# user.net
KiCad netlist of a schematic drawn in Altium Designer
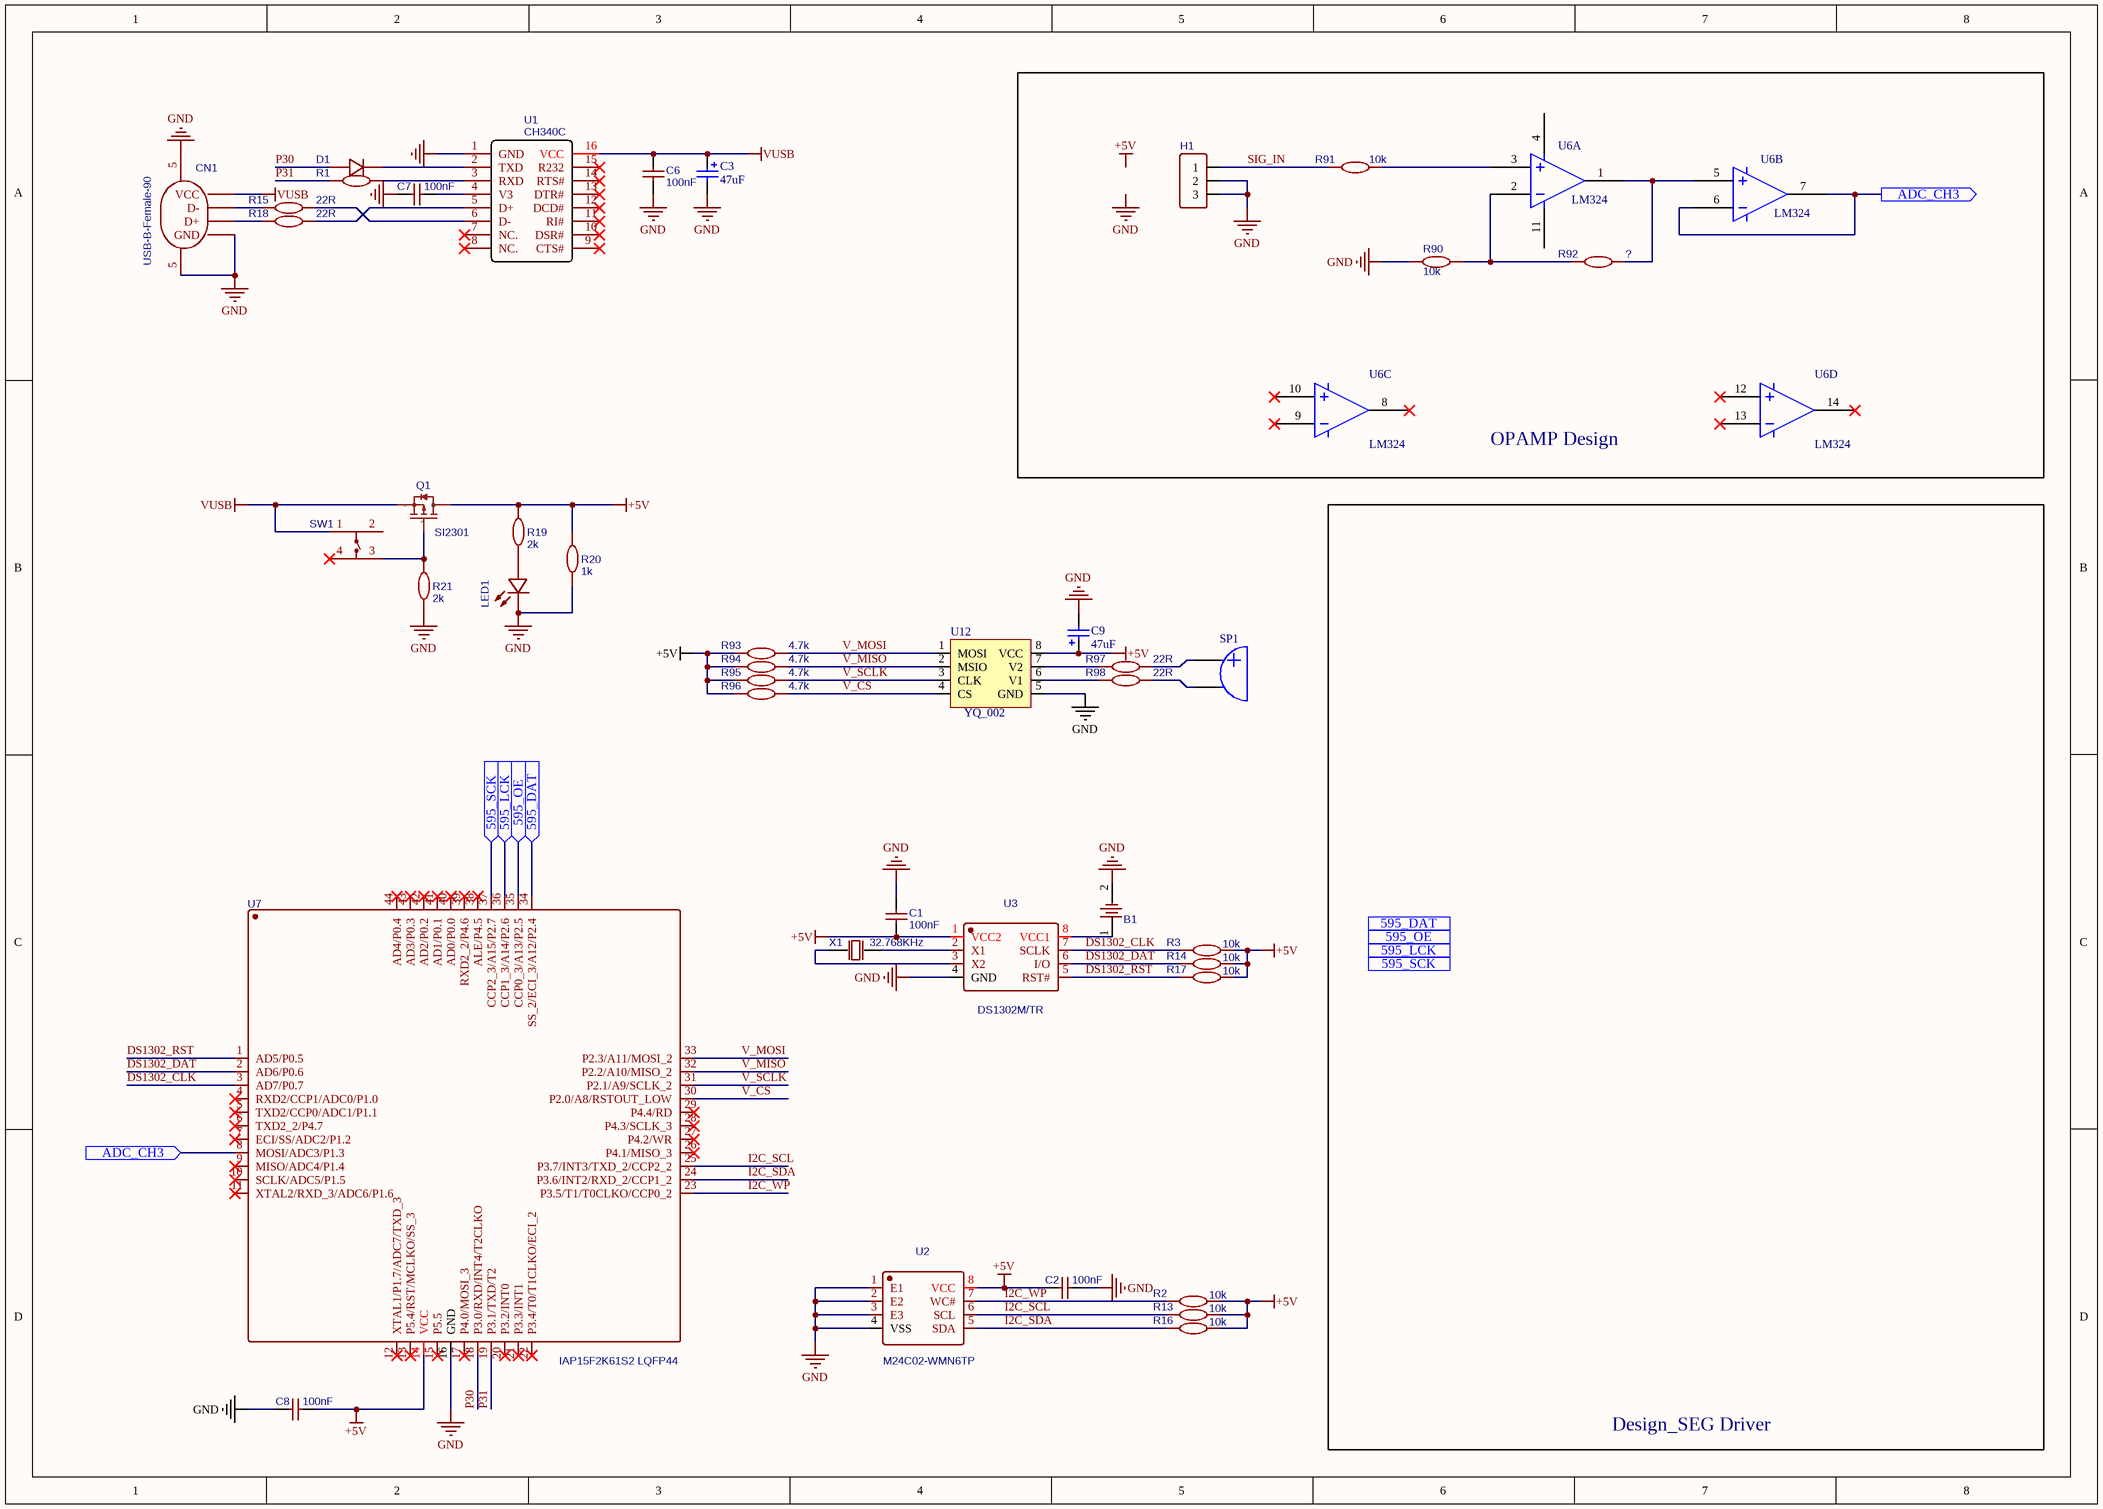
[diagram p0: user.SchDoc]

(export (version "E")
  (design (tool "Eeschema 10.0.6"))
  (components
    (comp (ref "B1")
      (value "CR1220-2")
      (fields (field (name "BOM_SUPPLIER PART") "C70381"))
      (libsource (lib "altium-import") (part "root_1_CR1220-2_"))
    )
    (comp (ref "C1")
      (value "100nF")
      (fields
        (field (name "BOM_MANUFACTURER PART") "0805F104M500NT")
        (field (name "BOM_SUPPLIER PART") "C28378")
      )
      (libsource (lib "altium-import") (part "root_1_100nF_"))
    )
    (comp (ref "C2")
      (value "100nF")
      (fields
        (field (name "BOM_MANUFACTURER PART") "0805F104M500NT")
        (field (name "BOM_SUPPLIER PART") "C28378")
      )
      (libsource (lib "altium-import") (part "root_0_100nF_"))
    )
    (comp (ref "C3")
      (value "47uF")
      (description "Polarized Capacitor (Axial)")
      (libsource (lib "Miscellaneous Devices") (part "Cap Pol2"))
    )
    (comp (ref "C6")
      (value "100nF")
      (fields
        (field (name "BOM_MANUFACTURER PART") "0805F104M500NT")
        (field (name "BOM_SUPPLIER PART") "C28378")
      )
      (libsource (lib "altium-import") (part "root_1_100nF_"))
    )
    (comp (ref "C7")
      (value "100nF")
      (fields
        (field (name "BOM_MANUFACTURER PART") "0805F104M500NT")
        (field (name "BOM_SUPPLIER PART") "C28378")
      )
      (libsource (lib "altium-import") (part "root_0_100nF_"))
    )
    (comp (ref "C8")
      (value "100nF")
      (fields
        (field (name "BOM_MANUFACTURER PART") "0805F104M500NT")
        (field (name "BOM_SUPPLIER PART") "C28378")
      )
      (libsource (lib "altium-import") (part "root_0_100nF_"))
    )
    (comp (ref "C9")
      (value "47uF")
      (description "Polarized Capacitor (Axial)")
      (libsource (lib "Miscellaneous Devices") (part "Cap Pol2"))
    )
    (comp (ref "CN1")
      (value "USB-B-Female-90")
      (fields (field (name "BOM_MANUFACTURER PART") "USB-BF90") (field (name "BOM_SUPPLIER PART") "C46392"))
      (libsource (lib "altium-import") (part "root_0_USB-B-Female-90_"))
    )
    (comp (ref "D1")
      (value "KLL4148")
      (fields (field (name "BOM_SUPPLIER PART") "C369941") (field (name "CONTRIBUTOR") "LCSC"))
      (libsource (lib "altium-import") (part "root_2_KLL4148_"))
    )
    (comp (ref "H1")
      (value "HDR-F-2.54_1x3")
      (fields (field (name "BOM_SUPPLIER PART") "C146690") (field (name "CONTRIBUTOR") "LCEDA_Lib"))
      (libsource (lib "CT105") (part "HDR-F-2.54_1x3"))
    )
    (comp (ref "LED1")
      (value "17-21URC/TR8")
      (fields (field (name "BOM_SUPPLIER PART") "C264414") (field (name "CONTRIBUTOR") "LCSC"))
      (libsource (lib "altium-import") (part "root_1_17-21URC/TR8_"))
    )
    (comp (ref "Q1")
      (value "SI2301")
      (fields (field (name "BOM_SUPPLIER PART") "C181086") (field (name "CONTRIBUTOR") "LCSC"))
      (libsource (lib "altium-import") (part "root_1_SI2301_"))
    )
    (comp (ref "R1")
      (value "1k")
      (fields
        (field (name "BOM_MANUFACTURER PART") "080500J0104T5E")
        (field (name "BOM_SUPPLIER PART") "C149503")
        (field (name "CONTRIBUTOR") "LCSC")
      )
      (libsource (lib "altium-import") (part "root_2_1k_"))
    )
    (comp (ref "R2")
      (value "10k")
      (fields
        (field (name "BOM_MANUFACTURER PART") "080500J0104T5E")
        (field (name "BOM_SUPPLIER PART") "C149503")
        (field (name "CONTRIBUTOR") "LCSC")
      )
      (libsource (lib "altium-import") (part "root_0_10k_"))
    )
    (comp (ref "R3")
      (value "10k")
      (fields
        (field (name "BOM_MANUFACTURER PART") "080500J0104T5E")
        (field (name "BOM_SUPPLIER PART") "C149503")
        (field (name "CONTRIBUTOR") "LCSC")
      )
      (libsource (lib "altium-import") (part "root_0_10k_"))
    )
    (comp (ref "R13")
      (value "10k")
      (fields
        (field (name "BOM_MANUFACTURER PART") "080500J0104T5E")
        (field (name "BOM_SUPPLIER PART") "C149503")
        (field (name "CONTRIBUTOR") "LCSC")
      )
      (libsource (lib "altium-import") (part "root_0_10k_"))
    )
    (comp (ref "R14")
      (value "10k")
      (fields
        (field (name "BOM_MANUFACTURER PART") "080500J0104T5E")
        (field (name "BOM_SUPPLIER PART") "C149503")
        (field (name "CONTRIBUTOR") "LCSC")
      )
      (libsource (lib "altium-import") (part "root_0_10k_"))
    )
    (comp (ref "R15")
      (value "22R")
      (fields
        (field (name "BOM_MANUFACTURER PART") "080500J0104T5E")
        (field (name "BOM_SUPPLIER PART") "C149503")
        (field (name "CONTRIBUTOR") "LCSC")
      )
      (libsource (lib "altium-import") (part "root_2_1k_"))
    )
    (comp (ref "R16")
      (value "10k")
      (fields
        (field (name "BOM_MANUFACTURER PART") "080500J0104T5E")
        (field (name "BOM_SUPPLIER PART") "C149503")
        (field (name "CONTRIBUTOR") "LCSC")
      )
      (libsource (lib "altium-import") (part "root_0_10k_"))
    )
    (comp (ref "R17")
      (value "10k")
      (fields
        (field (name "BOM_MANUFACTURER PART") "080500J0104T5E")
        (field (name "BOM_SUPPLIER PART") "C149503")
        (field (name "CONTRIBUTOR") "LCSC")
      )
      (libsource (lib "altium-import") (part "root_0_10k_"))
    )
    (comp (ref "R18")
      (value "22R")
      (fields
        (field (name "BOM_MANUFACTURER PART") "080500J0104T5E")
        (field (name "BOM_SUPPLIER PART") "C149503")
        (field (name "CONTRIBUTOR") "LCSC")
      )
      (libsource (lib "altium-import") (part "root_2_1k_"))
    )
    (comp (ref "R19")
      (value "2k")
      (fields
        (field (name "BOM_MANUFACTURER PART") "080500J0104T5E")
        (field (name "BOM_SUPPLIER PART") "C149503")
        (field (name "CONTRIBUTOR") "LCSC")
      )
      (libsource (lib "altium-import") (part "root_1_2k_"))
    )
    (comp (ref "R20")
      (value "1k")
      (fields
        (field (name "BOM_MANUFACTURER PART") "080500J0104T5E")
        (field (name "BOM_SUPPLIER PART") "C149503")
        (field (name "CONTRIBUTOR") "LCSC")
      )
      (libsource (lib "altium-import") (part "root_1_1k_"))
    )
    (comp (ref "R21")
      (value "2k")
      (fields
        (field (name "BOM_MANUFACTURER PART") "080500J0104T5E")
        (field (name "BOM_SUPPLIER PART") "C149503")
        (field (name "CONTRIBUTOR") "LCSC")
      )
      (libsource (lib "altium-import") (part "root_1_2k_"))
    )
    (comp (ref "R90")
      (value "10k")
      (fields
        (field (name "BOM_MANUFACTURER PART") "080500J0104T5E")
        (field (name "BOM_SUPPLIER PART") "C149503")
        (field (name "CONTRIBUTOR") "LCSC")
      )
      (libsource (lib "altium-import") (part "root_2_1k_"))
    )
    (comp (ref "R91")
      (value "10k")
      (fields
        (field (name "BOM_MANUFACTURER PART") "080500J0104T5E")
        (field (name "BOM_SUPPLIER PART") "C149503")
        (field (name "CONTRIBUTOR") "LCSC")
      )
      (libsource (lib "altium-import") (part "root_2_1k_"))
    )
    (comp (ref "R92")
      (value "?")
      (fields
        (field (name "BOM_MANUFACTURER PART") "080500J0104T5E")
        (field (name "BOM_SUPPLIER PART") "C149503")
        (field (name "CONTRIBUTOR") "LCSC")
      )
      (libsource (lib "altium-import") (part "root_2_1k_"))
    )
    (comp (ref "R93")
      (value "4.7k")
      (fields
        (field (name "BOM_MANUFACTURER PART") "080500J0104T5E")
        (field (name "BOM_SUPPLIER PART") "C149503")
        (field (name "CONTRIBUTOR") "LCSC")
      )
      (libsource (lib "altium-import") (part "root_2_1k_"))
    )
    (comp (ref "R94")
      (value "4.7k")
      (fields
        (field (name "BOM_MANUFACTURER PART") "080500J0104T5E")
        (field (name "BOM_SUPPLIER PART") "C149503")
        (field (name "CONTRIBUTOR") "LCSC")
      )
      (libsource (lib "altium-import") (part "root_2_1k_"))
    )
    (comp (ref "R95")
      (value "4.7k")
      (fields
        (field (name "BOM_MANUFACTURER PART") "080500J0104T5E")
        (field (name "BOM_SUPPLIER PART") "C149503")
        (field (name "CONTRIBUTOR") "LCSC")
      )
      (libsource (lib "altium-import") (part "root_2_1k_"))
    )
    (comp (ref "R96")
      (value "4.7k")
      (fields
        (field (name "BOM_MANUFACTURER PART") "080500J0104T5E")
        (field (name "BOM_SUPPLIER PART") "C149503")
        (field (name "CONTRIBUTOR") "LCSC")
      )
      (libsource (lib "altium-import") (part "root_2_1k_"))
    )
    (comp (ref "R97")
      (value "22R")
      (fields
        (field (name "BOM_MANUFACTURER PART") "080500J0104T5E")
        (field (name "BOM_SUPPLIER PART") "C149503")
        (field (name "CONTRIBUTOR") "LCSC")
      )
      (libsource (lib "altium-import") (part "root_0_1k_"))
    )
    (comp (ref "R98")
      (value "22R")
      (fields
        (field (name "BOM_MANUFACTURER PART") "080500J0104T5E")
        (field (name "BOM_SUPPLIER PART") "C149503")
        (field (name "CONTRIBUTOR") "LCSC")
      )
      (libsource (lib "altium-import") (part "root_0_1k_"))
    )
    (comp (ref "SP1") (value "BUZZER") (description "Buzzer") (libsource (lib "*") (part "BUZZER")))
    (comp (ref "SW1")
      (value "TS-1159UB-B-D-BL")
      (fields (field (name "BOM_SUPPLIER PART") "C692480") (field (name "CONTRIBUTOR") "LCSC"))
      (libsource (lib "altium-import") (part "root_0_TS-1159UB-B-D-BL_"))
    )
    (comp (ref "U1")
      (value "CH340C")
      (fields (field (name "BOM_SUPPLIER PART") "C84681"))
      (libsource (lib "altium-import") (part "root_0_CH340C_"))
    )
    (comp (ref "U2")
      (value "M24C02-WMN6TP")
      (fields (field (name "BOM_SUPPLIER PART") "C7562"))
      (libsource (lib "altium-import") (part "root_0_M24C02-WMN6TP_"))
    )
    (comp (ref "U3")
      (value "DS1302M/TR")
      (fields (field (name "BOM_SUPPLIER PART") "C434511") (field (name "CONTRIBUTOR") "LCSC"))
      (libsource (lib "altium-import") (part "root_0_DS1302M/TR_"))
    )
    (comp (ref "U6") (value "LM324") (libsource (lib "*") (part "LM124")))
    (comp (ref "U7")
      (value "IAP15F2K61S2 LQFP44")
      (fields (field (name "BOM_SUPPLIER PART") "C47451"))
      (libsource (lib "altium-import") (part "root_0_IAP15F2K61S2 LQFP44_"))
    )
    (comp (ref "U12") (value "YQ_002") (libsource (lib "CT105") (part "LQ2021")))
    (comp (ref "X1")
      (value "32.768KHz")
      (fields
        (field (name "BOM_SUPPLIER PART") "C252404")
        (field (name "BOM_MANUFACTURER PART") "6K832768F12UB")
        (field (name "CONTRIBUTOR") "LCSC")
      )
      (libsource (lib "altium-import") (part "root_0_32.768KHz_"))
    )
  )
  (nets
    (net (code "1") (name "+5V") (class "Default")
      (node (ref "C1") (pin "1") (pinfunction "1_1") (pintype "passive"))
      (node (ref "C2") (pin "1") (pinfunction "1_1") (pintype "passive"))
      (node (ref "C8") (pin "2") (pinfunction "2_2") (pintype "passive"))
      (node (ref "C9") (pin "1") (pinfunction "1_1") (pintype "passive"))
      (node (ref "Q1") (pin "3") (pinfunction "D_3") (pintype "passive"))
      (node (ref "R13") (pin "2") (pinfunction "2_2") (pintype "passive"))
      (node (ref "R14") (pin "2") (pinfunction "2_2") (pintype "passive"))
      (node (ref "R16") (pin "2") (pinfunction "2_2") (pintype "passive"))
      (node (ref "R17") (pin "2") (pinfunction "2_2") (pintype "passive"))
      (node (ref "R19") (pin "2") (pinfunction "2_2") (pintype "passive"))
      (node (ref "R2") (pin "2") (pinfunction "2_2") (pintype "passive"))
      (node (ref "R20") (pin "2") (pinfunction "2_2") (pintype "passive"))
      (node (ref "R3") (pin "2") (pinfunction "2_2") (pintype "passive"))
      (node (ref "R93") (pin "2") (pinfunction "2_2") (pintype "passive"))
      (node (ref "R94") (pin "2") (pinfunction "2_2") (pintype "passive"))
      (node (ref "R95") (pin "2") (pinfunction "2_2") (pintype "passive"))
      (node (ref "R96") (pin "2") (pinfunction "2_2") (pintype "passive"))
      (node (ref "U12") (pin "8") (pinfunction "VCC_8") (pintype "passive"))
      (node (ref "U2") (pin "8") (pinfunction "VCC_8") (pintype "passive"))
      (node (ref "U3") (pin "1") (pinfunction "VCC2_1") (pintype "passive"))
      (node (ref "U7") (pin "14") (pinfunction "VCC_14") (pintype "passive"))
    )
    (net (code "2") (name "/595_DAT") (class "Default")
      (node (ref "U7") (pin "34") (pinfunction "SS_2/ECI_3/A12/P2.4_34") (pintype "passive"))
    )
    (net (code "3") (name "/595_LCK") (class "Default")
      (node (ref "U7") (pin "36") (pinfunction "CCP1_3/A14/P2.6_36") (pintype "passive"))
    )
    (net (code "4") (name "/595_OE") (class "Default")
      (node (ref "U7") (pin "35") (pinfunction "CCP0_3/A13/P2.5_35") (pintype "passive"))
    )
    (net (code "5") (name "/595_SCK") (class "Default")
      (node (ref "U7") (pin "37") (pinfunction "CCP2_3/A15/P2.7_37") (pintype "passive"))
    )
    (net (code "6") (name "/ADC_CH3") (class "Default")
      (node (ref "U6") (pin "6") (pintype "passive"))
      (node (ref "U6") (pin "7") (pintype "passive"))
      (node (ref "U7") (pin "8") (pinfunction "MOSI/ADC3/P1.3_8") (pintype "passive"))
    )
    (net (code "7") (name "/DS1302_CLK") (class "Default")
      (node (ref "R3") (pin "1") (pinfunction "1_1") (pintype "passive"))
      (node (ref "U3") (pin "7") (pinfunction "SCLK_7") (pintype "passive"))
      (node (ref "U7") (pin "3") (pinfunction "AD7/P0.7_3") (pintype "passive"))
    )
    (net (code "8") (name "/DS1302_DAT") (class "Default")
      (node (ref "R14") (pin "1") (pinfunction "1_1") (pintype "passive"))
      (node (ref "U3") (pin "6") (pinfunction "I/O_6") (pintype "passive"))
      (node (ref "U7") (pin "2") (pinfunction "AD6/P0.6_2") (pintype "passive"))
    )
    (net (code "9") (name "/DS1302_RST") (class "Default")
      (node (ref "R17") (pin "1") (pinfunction "1_1") (pintype "passive"))
      (node (ref "U3") (pin "5") (pinfunction "RST#_5") (pintype "passive"))
      (node (ref "U7") (pin "1") (pinfunction "AD5/P0.5_1") (pintype "passive"))
    )
    (net (code "10") (name "/I2C_SCL") (class "Default")
      (node (ref "R13") (pin "1") (pinfunction "1_1") (pintype "passive"))
      (node (ref "U2") (pin "6") (pinfunction "SCL_6") (pintype "passive"))
      (node (ref "U7") (pin "25") (pinfunction "P3.7/INT3/TXD_2/CCP2_2_25") (pintype "passive"))
    )
    (net (code "11") (name "/I2C_SDA") (class "Default")
      (node (ref "R16") (pin "1") (pinfunction "1_1") (pintype "passive"))
      (node (ref "U2") (pin "5") (pinfunction "SDA_5") (pintype "passive"))
      (node (ref "U7") (pin "24") (pinfunction "P3.6/INT2/RXD_2/CCP1_2_24") (pintype "passive"))
    )
    (net (code "12") (name "/I2C_WP") (class "Default")
      (node (ref "R2") (pin "1") (pinfunction "1_1") (pintype "passive"))
      (node (ref "U2") (pin "7") (pinfunction "WC#_7") (pintype "passive"))
      (node (ref "U7") (pin "23") (pinfunction "P3.5/T1/T0CLKO/CCP0_2_23") (pintype "passive"))
    )
    (net (code "13") (name "/P30") (class "Default")
      (node (ref "D1") (pin "2") (pinfunction "A_2") (pintype "passive"))
      (node (ref "U7") (pin "18") (pinfunction "P3.0/RXD/INT4/T2CLKO_18") (pintype "passive"))
    )
    (net (code "14") (name "/P31") (class "Default")
      (node (ref "R1") (pin "2") (pinfunction "2_2") (pintype "passive"))
      (node (ref "U7") (pin "19") (pinfunction "P3.1/TXD/T2_19") (pintype "passive"))
    )
    (net (code "15") (name "/SIG_IN") (class "Default")
      (node (ref "H1") (pin "1") (pinfunction "1_1") (pintype "passive"))
      (node (ref "R91") (pin "2") (pinfunction "2_2") (pintype "passive"))
    )
    (net (code "16") (name "/V_CS") (class "Default")
      (node (ref "R96") (pin "1") (pinfunction "1_1") (pintype "passive"))
      (node (ref "U12") (pin "4") (pinfunction "CS_4") (pintype "passive"))
      (node (ref "U7") (pin "30") (pinfunction "P2.0/A8/RSTOUT_LOW_30") (pintype "passive"))
    )
    (net (code "17") (name "/V_MISO") (class "Default")
      (node (ref "R94") (pin "1") (pinfunction "1_1") (pintype "passive"))
      (node (ref "U12") (pin "2") (pinfunction "MSIO_2") (pintype "passive"))
      (node (ref "U7") (pin "32") (pinfunction "P2.2/A10/MISO_2_32") (pintype "passive"))
    )
    (net (code "18") (name "/V_MOSI") (class "Default")
      (node (ref "R93") (pin "1") (pinfunction "1_1") (pintype "passive"))
      (node (ref "U12") (pin "1") (pinfunction "MOSI_1") (pintype "passive"))
      (node (ref "U7") (pin "33") (pinfunction "P2.3/A11/MOSI_2_33") (pintype "passive"))
    )
    (net (code "19") (name "/V_SCLK") (class "Default")
      (node (ref "R95") (pin "1") (pinfunction "1_1") (pintype "passive"))
      (node (ref "U12") (pin "3") (pinfunction "CLK_3") (pintype "passive"))
      (node (ref "U7") (pin "31") (pinfunction "P2.1/A9/SCLK_2_31") (pintype "passive"))
    )
    (net (code "20") (name "GND") (class "Default")
      (node (ref "B1") (pin "2") (pinfunction "2_2") (pintype "passive"))
      (node (ref "C1") (pin "2") (pinfunction "2_2") (pintype "passive"))
      (node (ref "C2") (pin "2") (pinfunction "2_2") (pintype "passive"))
      (node (ref "C3") (pin "2") (pinfunction "2_2") (pintype "passive"))
      (node (ref "C6") (pin "1") (pinfunction "1_1") (pintype "passive"))
      (node (ref "C7") (pin "1") (pinfunction "1_1") (pintype "passive"))
      (node (ref "C8") (pin "1") (pinfunction "1_1") (pintype "passive"))
      (node (ref "C9") (pin "2") (pinfunction "2_2") (pintype "passive"))
      (node (ref "CN1") (pin "4") (pinfunction "GND_4") (pintype "passive"))
      (node (ref "CN1") (pin "5") (pinfunction "SH2_5") (pintype "passive"))
      (node (ref "H1") (pin "2") (pinfunction "2_2") (pintype "passive"))
      (node (ref "H1") (pin "3") (pinfunction "3_3") (pintype "passive"))
      (node (ref "LED1") (pin "2") (pinfunction "K_2") (pintype "passive"))
      (node (ref "R20") (pin "1") (pinfunction "1_1") (pintype "passive"))
      (node (ref "R21") (pin "1") (pinfunction "1_1") (pintype "passive"))
      (node (ref "R90") (pin "2") (pinfunction "2_2") (pintype "passive"))
      (node (ref "U1") (pin "1") (pinfunction "GND_1") (pintype "passive"))
      (node (ref "U12") (pin "5") (pinfunction "GND_5") (pintype "passive"))
      (node (ref "U2") (pin "1") (pinfunction "E1_1") (pintype "passive"))
      (node (ref "U2") (pin "2") (pinfunction "E2_2") (pintype "passive"))
      (node (ref "U2") (pin "3") (pinfunction "E3_3") (pintype "passive"))
      (node (ref "U2") (pin "4") (pinfunction "VSS_4") (pintype "passive"))
      (node (ref "U3") (pin "4") (pinfunction "GND_4") (pintype "passive"))
      (node (ref "U7") (pin "16") (pinfunction "GND_16") (pintype "passive"))
    )
    (net (code "21") (name "Net-(CN1-D+)") (class "Default")
      (node (ref "CN1") (pin "3") (pinfunction "D+_3") (pintype "passive"))
      (node (ref "R18") (pin "2") (pinfunction "2_2") (pintype "passive"))
    )
    (net (code "22") (name "Net-(CN1-D-)") (class "Default")
      (node (ref "CN1") (pin "2") (pinfunction "D-_2") (pintype "passive"))
      (node (ref "R15") (pin "2") (pinfunction "2_2") (pintype "passive"))
    )
    (net (code "23") (name "Net-(D1-C)") (class "Default")
      (node (ref "D1") (pin "1") (pinfunction "C_1") (pintype "passive"))
      (node (ref "U1") (pin "2") (pinfunction "TXD_2") (pintype "passive"))
    )
    (net (code "24") (name "Net-(LED1-A)") (class "Default")
      (node (ref "LED1") (pin "1") (pinfunction "A_1") (pintype "passive"))
      (node (ref "R19") (pin "1") (pinfunction "1_1") (pintype "passive"))
    )
    (net (code "25") (name "Net-(Q1-G)") (class "Default")
      (node (ref "Q1") (pin "1") (pinfunction "G_1") (pintype "passive"))
      (node (ref "R21") (pin "2") (pinfunction "2_2") (pintype "passive"))
      (node (ref "SW1") (pin "3") (pinfunction "3_3") (pintype "passive"))
    )
    (net (code "26") (name "Net-(R90-Pad1)") (class "Default")
      (node (ref "R90") (pin "1") (pinfunction "1_1") (pintype "passive"))
      (node (ref "R92") (pin "2") (pinfunction "2_2") (pintype "passive"))
      (node (ref "U6") (pin "2") (pintype "passive"))
    )
    (net (code "27") (name "Net-(R91-Pad1)") (class "Default")
      (node (ref "R91") (pin "1") (pinfunction "1_1") (pintype "passive"))
      (node (ref "U6") (pin "3") (pintype "passive"))
    )
    (net (code "28") (name "Net-(R92-Pad1)") (class "Default")
      (node (ref "R92") (pin "1") (pinfunction "1_1") (pintype "passive"))
      (node (ref "U6") (pin "1") (pintype "passive"))
      (node (ref "U6") (pin "5") (pintype "passive"))
    )
    (net (code "29") (name "Net-(R97-Pad2)") (class "Default")
      (node (ref "R97") (pin "2") (pinfunction "2_2") (pintype "passive"))
      (node (ref "SP1") (pin "1") (pinfunction "1_1") (pintype "passive"))
    )
    (net (code "30") (name "Net-(R98-Pad2)") (class "Default")
      (node (ref "R98") (pin "2") (pinfunction "2_2") (pintype "passive"))
      (node (ref "SP1") (pin "2") (pinfunction "2_2") (pintype "passive"))
    )
    (net (code "31") (name "Net-(U1-D+)") (class "Default")
      (node (ref "R18") (pin "1") (pinfunction "1_1") (pintype "passive"))
      (node (ref "U1") (pin "5") (pinfunction "D+_5") (pintype "passive"))
    )
    (net (code "32") (name "Net-(U1-D-)") (class "Default")
      (node (ref "R15") (pin "1") (pinfunction "1_1") (pintype "passive"))
      (node (ref "U1") (pin "6") (pinfunction "D-_6") (pintype "passive"))
    )
    (net (code "33") (name "Net-(U1-RXD)") (class "Default")
      (node (ref "R1") (pin "1") (pinfunction "1_1") (pintype "passive"))
      (node (ref "U1") (pin "3") (pinfunction "RXD_3") (pintype "passive"))
    )
    (net (code "34") (name "Net-(U1-V3)") (class "Default")
      (node (ref "C7") (pin "2") (pinfunction "2_2") (pintype "passive"))
      (node (ref "U1") (pin "4") (pinfunction "V3_4") (pintype "passive"))
    )
    (net (code "35") (name "Net-(U3-VCC1)") (class "Default")
      (node (ref "B1") (pin "1") (pinfunction "1_1") (pintype "passive"))
      (node (ref "U3") (pin "8") (pinfunction "VCC1_8") (pintype "passive"))
    )
    (net (code "36") (name "Net-(U3-X1)") (class "Default")
      (node (ref "U3") (pin "2") (pinfunction "X1_2") (pintype "passive"))
      (node (ref "X1") (pin "2") (pinfunction "OSC2_2") (pintype "passive"))
    )
    (net (code "37") (name "Net-(U3-X2)") (class "Default")
      (node (ref "U3") (pin "3") (pinfunction "X2_3") (pintype "passive"))
      (node (ref "X1") (pin "1") (pinfunction "OSC1_1") (pintype "passive"))
    )
    (net (code "38") (name "Net-(U12-V1)") (class "Default")
      (node (ref "R98") (pin "1") (pinfunction "1_1") (pintype "passive"))
      (node (ref "U12") (pin "6") (pinfunction "V1_6") (pintype "passive"))
    )
    (net (code "39") (name "Net-(U12-V2)") (class "Default")
      (node (ref "R97") (pin "1") (pinfunction "1_1") (pintype "passive"))
      (node (ref "U12") (pin "7") (pinfunction "V2_7") (pintype "passive"))
    )
    (net (code "40") (name "VUSB") (class "Default")
      (node (ref "C3") (pin "1") (pinfunction "1_1") (pintype "passive"))
      (node (ref "C6") (pin "2") (pinfunction "2_2") (pintype "passive"))
      (node (ref "CN1") (pin "1") (pinfunction "VCC_1") (pintype "passive"))
      (node (ref "Q1") (pin "2") (pinfunction "S_2") (pintype "passive"))
      (node (ref "SW1") (pin "1") (pinfunction "1_1") (pintype "passive"))
      (node (ref "U1") (pin "16") (pinfunction "VCC_16") (pintype "passive"))
    )
    (net (code "41") (name "unconnected-(SW1-Pad2)") (class "Default")
      (node (ref "SW1") (pin "2") (pinfunction "2_2") (pintype "passive"))
    )
    (net (code "42") (name "unconnected-(SW1-Pad4)") (class "Default")
      (node (ref "SW1") (pin "4") (pinfunction "4_4") (pintype "passive+no_connect"))
    )
    (net (code "43") (name "unconnected-(U1-CTS#-Pad9)") (class "Default")
      (node (ref "U1") (pin "9") (pinfunction "CTS#_9") (pintype "passive+no_connect"))
    )
    (net (code "44") (name "unconnected-(U1-DCD#-Pad12)") (class "Default")
      (node (ref "U1") (pin "12") (pinfunction "DCD#_12") (pintype "passive+no_connect"))
    )
    (net (code "45") (name "unconnected-(U1-DSR#-Pad10)") (class "Default")
      (node (ref "U1") (pin "10") (pinfunction "DSR#_10") (pintype "passive+no_connect"))
    )
    (net (code "46") (name "unconnected-(U1-DTR#-Pad13)") (class "Default")
      (node (ref "U1") (pin "13") (pinfunction "DTR#_13") (pintype "passive+no_connect"))
    )
    (net (code "47") (name "unconnected-(U1-NC.-Pad7)") (class "Default")
      (node (ref "U1") (pin "7") (pinfunction "NC._7") (pintype "passive+no_connect"))
    )
    (net (code "48") (name "unconnected-(U1-NC.-Pad8)") (class "Default")
      (node (ref "U1") (pin "8") (pinfunction "NC._8") (pintype "passive+no_connect"))
    )
    (net (code "49") (name "unconnected-(U1-R232-Pad15)") (class "Default")
      (node (ref "U1") (pin "15") (pinfunction "R232_15") (pintype "passive+no_connect"))
    )
    (net (code "50") (name "unconnected-(U1-RI#-Pad11)") (class "Default")
      (node (ref "U1") (pin "11") (pinfunction "RI#_11") (pintype "passive+no_connect"))
    )
    (net (code "51") (name "unconnected-(U1-RTS#-Pad14)") (class "Default")
      (node (ref "U1") (pin "14") (pinfunction "RTS#_14") (pintype "passive+no_connect"))
    )
    (net (code "52") (name "unconnected-(U6-Pad4)") (class "Default")
      (node (ref "U6") (pin "4") (pintype "passive"))
    )
    (net (code "53") (name "unconnected-(U6-Pad8)") (class "Default")
      (node (ref "U6") (pin "8") (pintype "passive+no_connect"))
    )
    (net (code "54") (name "unconnected-(U6-Pad9)") (class "Default")
      (node (ref "U6") (pin "9") (pintype "passive+no_connect"))
    )
    (net (code "55") (name "unconnected-(U6-Pad10)") (class "Default")
      (node (ref "U6") (pin "10") (pintype "passive+no_connect"))
    )
    (net (code "56") (name "unconnected-(U6-Pad11)") (class "Default")
      (node (ref "U6") (pin "11") (pintype "passive"))
    )
    (net (code "57") (name "unconnected-(U6-Pad12)") (class "Default")
      (node (ref "U6") (pin "12") (pintype "passive+no_connect"))
    )
    (net (code "58") (name "unconnected-(U6-Pad13)") (class "Default")
      (node (ref "U6") (pin "13") (pintype "passive+no_connect"))
    )
    (net (code "59") (name "unconnected-(U6-Pad14)") (class "Default")
      (node (ref "U6") (pin "14") (pintype "passive+no_connect"))
    )
    (net (code "60") (name "unconnected-(U7-AD0{slash}P0.0-Pad40)") (class "Default")
      (node (ref "U7") (pin "40") (pinfunction "AD0/P0.0_40") (pintype "passive+no_connect"))
    )
    (net (code "61") (name "unconnected-(U7-AD1{slash}P0.1-Pad41)") (class "Default")
      (node (ref "U7") (pin "41") (pinfunction "AD1/P0.1_41") (pintype "passive+no_connect"))
    )
    (net (code "62") (name "unconnected-(U7-AD2{slash}P0.2-Pad42)") (class "Default")
      (node (ref "U7") (pin "42") (pinfunction "AD2/P0.2_42") (pintype "passive+no_connect"))
    )
    (net (code "63") (name "unconnected-(U7-AD3{slash}P0.3-Pad43)") (class "Default")
      (node (ref "U7") (pin "43") (pinfunction "AD3/P0.3_43") (pintype "passive+no_connect"))
    )
    (net (code "64") (name "unconnected-(U7-AD4{slash}P0.4-Pad44)") (class "Default")
      (node (ref "U7") (pin "44") (pinfunction "AD4/P0.4_44") (pintype "passive+no_connect"))
    )
    (net (code "65") (name "unconnected-(U7-ALE{slash}P4.5-Pad38)") (class "Default")
      (node (ref "U7") (pin "38") (pinfunction "ALE/P4.5_38") (pintype "passive+no_connect"))
    )
    (net (code "66") (name "unconnected-(U7-ECI{slash}SS{slash}ADC2{slash}P1.2-Pad7)") (class "Default")
      (node (ref "U7") (pin "7") (pinfunction "ECI/SS/ADC2/P1.2_7") (pintype "passive+no_connect"))
    )
    (net (code "67") (name "unconnected-(U7-MISO{slash}ADC4{slash}P1.4-Pad9)") (class "Default")
      (node (ref "U7") (pin "9") (pinfunction "MISO/ADC4/P1.4_9") (pintype "passive+no_connect"))
    )
    (net (code "68") (name "unconnected-(U7-P3.2{slash}INT0-Pad20)") (class "Default")
      (node (ref "U7") (pin "20") (pinfunction "P3.2/INT0_20") (pintype "passive+no_connect"))
    )
    (net (code "69") (name "unconnected-(U7-P3.3{slash}INT1-Pad21)") (class "Default")
      (node (ref "U7") (pin "21") (pinfunction "P3.3/INT1_21") (pintype "passive+no_connect"))
    )
    (net (code "70") (name "unconnected-(U7-P3.4{slash}T0{slash}T1CLKO{slash}ECI_2-Pad22)") (class "Default")
      (node (ref "U7") (pin "22") (pinfunction "P3.4/T0/T1CLKO/ECI_2_22") (pintype "passive+no_connect"))
    )
    (net (code "71") (name "unconnected-(U7-P4.0{slash}MOSI_3-Pad17)") (class "Default")
      (node (ref "U7") (pin "17") (pinfunction "P4.0/MOSI_3_17") (pintype "passive+no_connect"))
    )
    (net (code "72") (name "unconnected-(U7-P4.1{slash}MISO_3-Pad26)") (class "Default")
      (node (ref "U7") (pin "26") (pinfunction "P4.1/MISO_3_26") (pintype "passive+no_connect"))
    )
    (net (code "73") (name "unconnected-(U7-P4.2{slash}WR-Pad27)") (class "Default")
      (node (ref "U7") (pin "27") (pinfunction "P4.2/WR_27") (pintype "passive+no_connect"))
    )
    (net (code "74") (name "unconnected-(U7-P4.3{slash}SCLK_3-Pad28)") (class "Default")
      (node (ref "U7") (pin "28") (pinfunction "P4.3/SCLK_3_28") (pintype "passive+no_connect"))
    )
    (net (code "75") (name "unconnected-(U7-P4.4{slash}RD-Pad29)") (class "Default")
      (node (ref "U7") (pin "29") (pinfunction "P4.4/RD_29") (pintype "passive+no_connect"))
    )
    (net (code "76") (name "unconnected-(U7-P5.4{slash}RST{slash}MCLKO{slash}SS_3-Pad13)") (class "Default")
      (node (ref "U7") (pin "13") (pinfunction "P5.4/RST/MCLKO/SS_3_13") (pintype "passive+no_connect"))
    )
    (net (code "77") (name "unconnected-(U7-P5.5-Pad15)") (class "Default")
      (node (ref "U7") (pin "15") (pinfunction "P5.5_15") (pintype "passive+no_connect"))
    )
    (net (code "78") (name "unconnected-(U7-RXD2_2{slash}P4.6-Pad39)") (class "Default")
      (node (ref "U7") (pin "39") (pinfunction "RXD2_2/P4.6_39") (pintype "passive+no_connect"))
    )
    (net (code "79") (name "unconnected-(U7-RXD2{slash}CCP1{slash}ADC0{slash}P1.0-Pad4)") (class "Default")
      (node (ref "U7") (pin "4") (pinfunction "RXD2/CCP1/ADC0/P1.0_4") (pintype "passive+no_connect"))
    )
    (net (code "80") (name "unconnected-(U7-SCLK{slash}ADC5{slash}P1.5-Pad10)") (class "Default")
      (node (ref "U7") (pin "10") (pinfunction "SCLK/ADC5/P1.5_10") (pintype "passive+no_connect"))
    )
    (net (code "81") (name "unconnected-(U7-TXD2_2{slash}P4.7-Pad6)") (class "Default")
      (node (ref "U7") (pin "6") (pinfunction "TXD2_2/P4.7_6") (pintype "passive+no_connect"))
    )
    (net (code "82") (name "unconnected-(U7-TXD2{slash}CCP0{slash}ADC1{slash}P1.1-Pad5)") (class "Default")
      (node (ref "U7") (pin "5") (pinfunction "TXD2/CCP0/ADC1/P1.1_5") (pintype "passive+no_connect"))
    )
    (net (code "83") (name "unconnected-(U7-XTAL1{slash}P1.7{slash}ADC7{slash}TXD_3-Pad12)") (class "Default")
      (node (ref "U7") (pin "12") (pinfunction "XTAL1/P1.7/ADC7/TXD_3_12") (pintype "passive+no_connect"))
    )
    (net (code "84") (name "unconnected-(U7-XTAL2{slash}RXD_3{slash}ADC6{slash}P1.6-Pad11)") (class "Default")
      (node (ref "U7") (pin "11") (pinfunction "XTAL2/RXD_3/ADC6/P1.6_11") (pintype "passive+no_connect"))
    )
  )
)
